# USB_U-Turn.net
KiCad netlist of a schematic drawn in Altium Designer
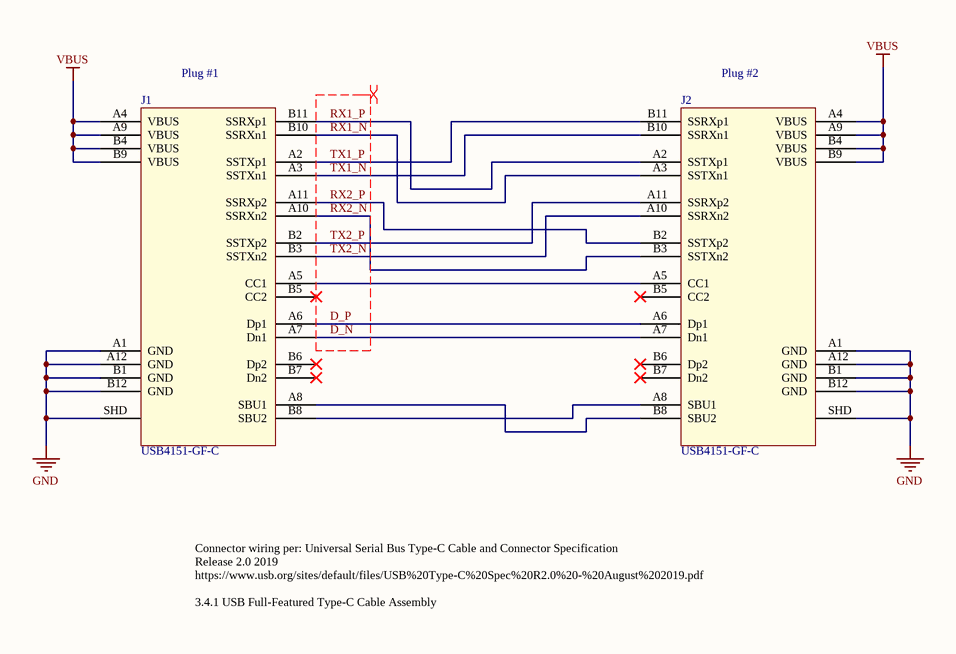
[diagram p0: USB U-Turn.SchDoc]

(export (version "E")
  (design (tool "Eeschema 10.0.6"))
  (components
    (comp (ref "J1")
      (value "USB4151-GF-C")
      (footprint "USB4151-GF-C")
      (description "USB TYPE C, PLUG, SMT , G/F, VER")
      (libsource (lib "KBuchka-IntLib") (part "USB4151-GF-C"))
    )
    (comp (ref "J2")
      (value "USB4151-GF-C")
      (footprint "USB4151-GF-C")
      (description "USB TYPE C, PLUG, SMT , G/F, VER")
      (libsource (lib "") (part "USB4151-GF-C_1"))
    )
  )
  (nets
    (net (code "1") (name "/D_N") (class "Default")
      (node (ref "J1") (pin "A7") (pinfunction "Dn1_A7") (pintype "passive"))
      (node (ref "J2") (pin "A7") (pinfunction "Dn1_A7") (pintype "passive"))
    )
    (net (code "2") (name "/D_P") (class "Default")
      (node (ref "J1") (pin "A6") (pinfunction "Dp1_A6") (pintype "passive"))
      (node (ref "J2") (pin "A6") (pinfunction "Dp1_A6") (pintype "passive"))
    )
    (net (code "3") (name "/RX1_N") (class "Default")
      (node (ref "J1") (pin "B10") (pinfunction "SSRXn1_B10") (pintype "passive"))
      (node (ref "J2") (pin "A3") (pinfunction "SSTXn1_A3") (pintype "passive"))
    )
    (net (code "4") (name "/RX1_P") (class "Default")
      (node (ref "J1") (pin "B11") (pinfunction "SSRXp1_B11") (pintype "passive"))
      (node (ref "J2") (pin "A2") (pinfunction "SSTXp1_A2") (pintype "passive"))
    )
    (net (code "5") (name "/RX2_N") (class "Default")
      (node (ref "J1") (pin "A10") (pinfunction "SSRXn2_A10") (pintype "passive"))
      (node (ref "J2") (pin "B3") (pinfunction "SSTXn2_B3") (pintype "passive"))
    )
    (net (code "6") (name "/RX2_P") (class "Default")
      (node (ref "J1") (pin "A11") (pinfunction "SSRXp2_A11") (pintype "passive"))
      (node (ref "J2") (pin "B2") (pinfunction "SSTXp2_B2") (pintype "passive"))
    )
    (net (code "7") (name "/TX1_N") (class "Default")
      (node (ref "J1") (pin "A3") (pinfunction "SSTXn1_A3") (pintype "passive"))
      (node (ref "J2") (pin "B10") (pinfunction "SSRXn1_B10") (pintype "passive"))
    )
    (net (code "8") (name "/TX1_P") (class "Default")
      (node (ref "J1") (pin "A2") (pinfunction "SSTXp1_A2") (pintype "passive"))
      (node (ref "J2") (pin "B11") (pinfunction "SSRXp1_B11") (pintype "passive"))
    )
    (net (code "9") (name "/TX2_N") (class "Default")
      (node (ref "J1") (pin "B3") (pinfunction "SSTXn2_B3") (pintype "passive"))
      (node (ref "J2") (pin "A10") (pinfunction "SSRXn2_A10") (pintype "passive"))
    )
    (net (code "10") (name "/TX2_P") (class "Default")
      (node (ref "J1") (pin "B2") (pinfunction "SSTXp2_B2") (pintype "passive"))
      (node (ref "J2") (pin "A11") (pinfunction "SSRXp2_A11") (pintype "passive"))
    )
    (net (code "11") (name "GND") (class "Default")
      (node (ref "J1") (pin "A1") (pinfunction "GND_A1") (pintype "passive"))
      (node (ref "J1") (pin "A12") (pinfunction "GND_A12") (pintype "passive"))
      (node (ref "J1") (pin "B1") (pinfunction "GND_B1") (pintype "passive"))
      (node (ref "J1") (pin "B12") (pinfunction "GND_B12") (pintype "passive"))
      (node (ref "J1") (pin "SHD") (pinfunction "B13_SHD") (pintype "passive"))
      (node (ref "J2") (pin "A1") (pinfunction "GND_A1") (pintype "passive"))
      (node (ref "J2") (pin "A12") (pinfunction "GND_A12") (pintype "passive"))
      (node (ref "J2") (pin "B1") (pinfunction "GND_B1") (pintype "passive"))
      (node (ref "J2") (pin "B12") (pinfunction "GND_B12") (pintype "passive"))
      (node (ref "J2") (pin "SHD") (pinfunction "B13_SHD") (pintype "passive"))
    )
    (net (code "12") (name "Net-(J1-CC1)") (class "Default")
      (node (ref "J1") (pin "A5") (pinfunction "CC1_A5") (pintype "passive"))
      (node (ref "J2") (pin "A5") (pinfunction "CC1_A5") (pintype "passive"))
    )
    (net (code "13") (name "Net-(J1-SBU1)") (class "Default")
      (node (ref "J1") (pin "A8") (pinfunction "SBU1_A8") (pintype "passive"))
      (node (ref "J2") (pin "B8") (pinfunction "SBU2_B8") (pintype "passive"))
    )
    (net (code "14") (name "Net-(J1-SBU2)") (class "Default")
      (node (ref "J1") (pin "B8") (pinfunction "SBU2_B8") (pintype "passive"))
      (node (ref "J2") (pin "A8") (pinfunction "SBU1_A8") (pintype "passive"))
    )
    (net (code "15") (name "VBUS") (class "Default")
      (node (ref "J1") (pin "A4") (pinfunction "VBUS_A4") (pintype "passive"))
      (node (ref "J1") (pin "A9") (pinfunction "VBUS_A9") (pintype "passive"))
      (node (ref "J1") (pin "B4") (pinfunction "VBUS_B4") (pintype "passive"))
      (node (ref "J1") (pin "B9") (pinfunction "VBUS_B9") (pintype "passive"))
      (node (ref "J2") (pin "A4") (pinfunction "VBUS_A4") (pintype "passive"))
      (node (ref "J2") (pin "A9") (pinfunction "VBUS_A9") (pintype "passive"))
      (node (ref "J2") (pin "B4") (pinfunction "VBUS_B4") (pintype "passive"))
      (node (ref "J2") (pin "B9") (pinfunction "VBUS_B9") (pintype "passive"))
    )
    (net (code "16") (name "unconnected-(J1-CC2-PadB5)") (class "Default")
      (node (ref "J1") (pin "B5") (pinfunction "CC2_B5") (pintype "passive+no_connect"))
    )
    (net (code "17") (name "unconnected-(J1-Dn2-PadB7)") (class "Default")
      (node (ref "J1") (pin "B7") (pinfunction "Dn2_B7") (pintype "passive+no_connect"))
    )
    (net (code "18") (name "unconnected-(J1-Dp2-PadB6)") (class "Default")
      (node (ref "J1") (pin "B6") (pinfunction "Dp2_B6") (pintype "passive+no_connect"))
    )
    (net (code "19") (name "unconnected-(J2-CC2-PadB5)") (class "Default")
      (node (ref "J2") (pin "B5") (pinfunction "CC2_B5") (pintype "passive+no_connect"))
    )
    (net (code "20") (name "unconnected-(J2-Dn2-PadB7)") (class "Default")
      (node (ref "J2") (pin "B7") (pinfunction "Dn2_B7") (pintype "passive+no_connect"))
    )
    (net (code "21") (name "unconnected-(J2-Dp2-PadB6)") (class "Default")
      (node (ref "J2") (pin "B6") (pinfunction "Dp2_B6") (pintype "passive+no_connect"))
    )
  )
)
